# serial_one_plug.net
KiCad netlist of a schematic drawn in EAGLE
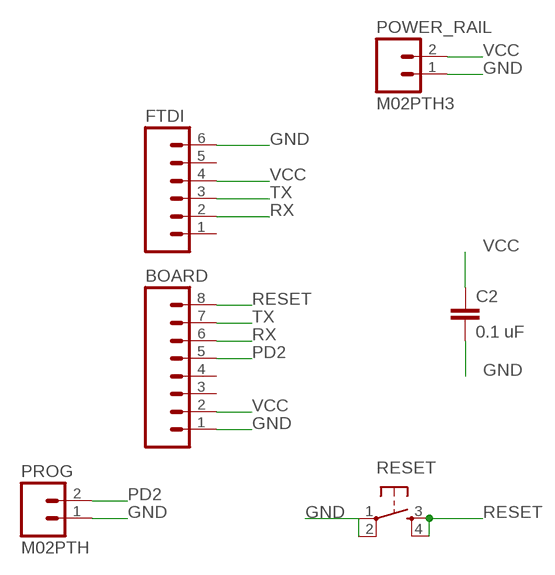
[diagram p0: schematic, sheet 1]

(export (version "E")
  (design (tool "Eeschema 10.0.6"))
  (components
    (comp (ref "BOARD")
      (value "M08LONGPADS")
      (footprint "eagle-import:1X08_LONGPADS")
      (libsource (lib "eagle-import") (part "M08LONGPADS"))
    )
    (comp (ref "C2")
      (value "0.1 uF")
      (footprint "eagle-import:C1206")
      (libsource (lib "eagle-import") (part "C-EUC1206"))
    )
    (comp (ref "FTDI")
      (value "M06LONGPADS")
      (footprint "eagle-import:1X06_LONGPADS")
      (libsource (lib "eagle-import") (part "M06LONGPADS"))
    )
    (comp (ref "POWER_RAIL")
      (value "M02PTH3")
      (footprint "eagle-import:1X02_LONGPADS")
      (libsource (lib "eagle-import") (part "M02PTH3"))
    )
    (comp (ref "PROG")
      (value "M02PTH")
      (footprint "eagle-import:1X02")
      (libsource (lib "eagle-import") (part "M02PTH"))
    )
    (comp (ref "RESET")
      (value "TAC_SWITCHPTH")
      (footprint "eagle-import:TACTILE-PTH")
      (libsource (lib "eagle-import") (part "TAC_SWITCHPTH"))
    )
  )
  (nets
    (net (code "1") (name "/GND") (class "Default")
      (node (ref "BOARD") (pin "1") (pinfunction "1_1") (pintype "passive"))
      (node (ref "C2") (pin "2") (pinfunction "2_2") (pintype "passive"))
      (node (ref "FTDI") (pin "6") (pinfunction "6_6") (pintype "passive"))
      (node (ref "POWER_RAIL") (pin "1") (pinfunction "1_1") (pintype "passive"))
      (node (ref "PROG") (pin "1") (pinfunction "1_1") (pintype "passive"))
      (node (ref "RESET") (pin "1") (pinfunction "1_1") (pintype "passive"))
      (node (ref "RESET") (pin "2") (pinfunction "2_2") (pintype "passive"))
    )
    (net (code "2") (name "/PD2") (class "Default")
      (node (ref "BOARD") (pin "5") (pinfunction "5_5") (pintype "passive"))
      (node (ref "PROG") (pin "2") (pinfunction "2_2") (pintype "passive"))
    )
    (net (code "3") (name "/RESET") (class "Default")
      (node (ref "BOARD") (pin "8") (pinfunction "8_8") (pintype "passive"))
      (node (ref "RESET") (pin "3") (pinfunction "3_3") (pintype "passive"))
      (node (ref "RESET") (pin "4") (pinfunction "4_4") (pintype "passive"))
    )
    (net (code "4") (name "/RX") (class "Default")
      (node (ref "BOARD") (pin "6") (pinfunction "6_6") (pintype "passive"))
      (node (ref "FTDI") (pin "2") (pinfunction "2_2") (pintype "passive"))
    )
    (net (code "5") (name "/TX") (class "Default")
      (node (ref "BOARD") (pin "7") (pinfunction "7_7") (pintype "passive"))
      (node (ref "FTDI") (pin "3") (pinfunction "3_3") (pintype "passive"))
    )
    (net (code "6") (name "/VCC") (class "Default")
      (node (ref "BOARD") (pin "2") (pinfunction "2_2") (pintype "passive"))
      (node (ref "C2") (pin "1") (pinfunction "1_1") (pintype "passive"))
      (node (ref "FTDI") (pin "4") (pinfunction "4_4") (pintype "passive"))
      (node (ref "POWER_RAIL") (pin "2") (pinfunction "2_2") (pintype "passive"))
    )
    (net (code "7") (name "unconnected-(BOARD-Pad3)") (class "Default")
      (node (ref "BOARD") (pin "3") (pinfunction "3_3") (pintype "passive"))
    )
    (net (code "8") (name "unconnected-(BOARD-Pad4)") (class "Default")
      (node (ref "BOARD") (pin "4") (pinfunction "4_4") (pintype "passive"))
    )
    (net (code "9") (name "unconnected-(FTDI-Pad1)") (class "Default")
      (node (ref "FTDI") (pin "1") (pinfunction "1_1") (pintype "passive"))
    )
    (net (code "10") (name "unconnected-(FTDI-Pad5)") (class "Default")
      (node (ref "FTDI") (pin "5") (pinfunction "5_5") (pintype "passive"))
    )
  )
)
